# rc2014_MCP4822.net
KiCad netlist of a schematic drawn in EAGLE
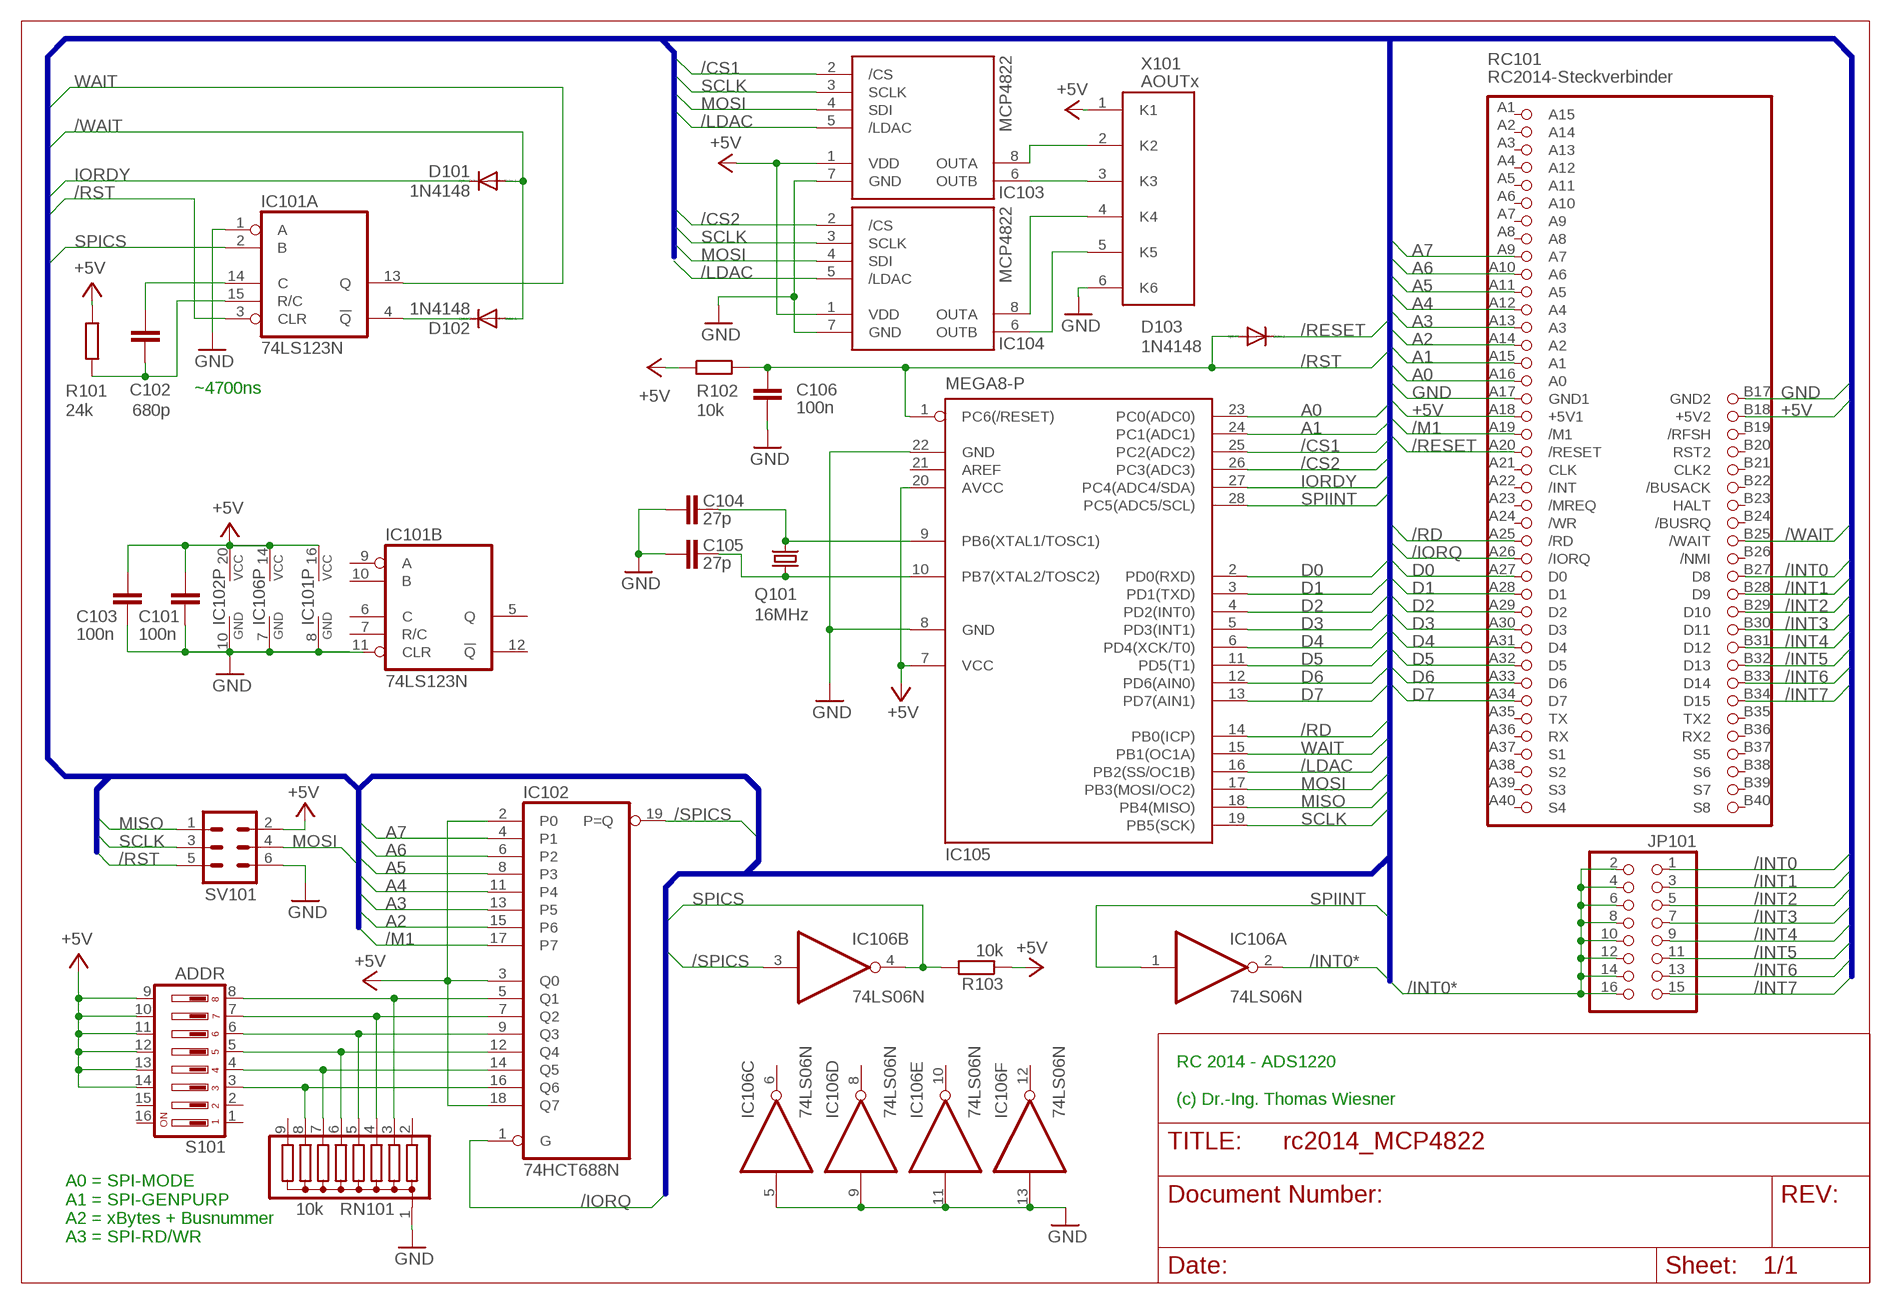
[diagram p0: schematic, sheet 1]

(export (version "E")
  (design (tool "Eeschema 10.0.6"))
  (components
    (comp (ref "C101")
      (value "100n")
      (footprint "eagle-import:C025-025X050")
      (libsource (lib "eagle-import") (part "C-EU025-025X050"))
    )
    (comp (ref "C102")
      (value "680p")
      (footprint "eagle-import:C025-025X050")
      (libsource (lib "eagle-import") (part "C-EU025-025X050"))
    )
    (comp (ref "C103")
      (value "100n")
      (footprint "eagle-import:C025-025X050")
      (libsource (lib "eagle-import") (part "C-EU025-025X050"))
    )
    (comp (ref "C104")
      (value "27p")
      (footprint "eagle-import:C025-025X050")
      (libsource (lib "eagle-import") (part "C-EU025-025X050"))
    )
    (comp (ref "C105")
      (value "27p")
      (footprint "eagle-import:C025-025X050")
      (libsource (lib "eagle-import") (part "C-EU025-025X050"))
    )
    (comp (ref "C106")
      (value "100n")
      (footprint "eagle-import:C025-025X050")
      (libsource (lib "eagle-import") (part "C-EU025-025X050"))
    )
    (comp (ref "D101")
      (value "1N4148")
      (footprint "eagle-import:DO35-10")
      (libsource (lib "eagle-import") (part "1N4148DO35-10"))
    )
    (comp (ref "D102")
      (value "1N4148")
      (footprint "eagle-import:DO35-10")
      (libsource (lib "eagle-import") (part "1N4148DO35-10"))
    )
    (comp (ref "D103")
      (value "1N4148")
      (footprint "eagle-import:DO35-10")
      (libsource (lib "eagle-import") (part "1N4148DO35-10"))
    )
    (comp (ref "IC101")
      (value "74LS123N")
      (footprint "eagle-import:DIL16")
      (libsource (lib "eagle-import") (part "74123NLS"))
    )
    (comp (ref "IC102")
      (value "74HCT688N")
      (footprint "eagle-import:DIL20")
      (libsource (lib "eagle-import") (part "74688NHCT"))
    )
    (comp (ref "IC103")
      (value "MCP4822")
      (footprint "eagle-import:DIL08")
      (libsource (lib "eagle-import") (part "MCP4822"))
    )
    (comp (ref "IC104")
      (value "MCP4822")
      (footprint "eagle-import:DIL08")
      (libsource (lib "eagle-import") (part "MCP4822"))
    )
    (comp (ref "IC105")
      (value "MEGA8-P")
      (footprint "eagle-import:DIL28-3")
      (libsource (lib "eagle-import") (part "MEGA8-P"))
    )
    (comp (ref "IC106")
      (value "74LS06N")
      (footprint "eagle-import:DIL14")
      (libsource (lib "eagle-import") (part "7406NLS"))
    )
    (comp (ref "JP101")
      (value "PINHD-2X8")
      (footprint "eagle-import:2X08")
      (libsource (lib "eagle-import") (part "PINHD-2X8"))
    )
    (comp (ref "Q101")
      (value "16MHz")
      (footprint "eagle-import:HC49U-V")
      (libsource (lib "eagle-import") (part "CRYSTALHC49U-V"))
    )
    (comp (ref "R101")
      (value "24k")
      (footprint "eagle-import:0207_10")
      (libsource (lib "eagle-import") (part "R-EU_0207/10"))
    )
    (comp (ref "R102")
      (value "10k")
      (footprint "eagle-import:0207_10")
      (libsource (lib "eagle-import") (part "R-EU_0207/10"))
    )
    (comp (ref "R103")
      (value "10k")
      (footprint "eagle-import:0207_10")
      (libsource (lib "eagle-import") (part "R-EU_0207/10"))
    )
    (comp (ref "RC101")
      (value "RC2014-Steckverbinder")
      (footprint "eagle-import:RC2014-STECKER")
      (libsource (lib "eagle-import") (part "RC2014STECKER"))
    )
    (comp (ref "RN101")
      (value "10k")
      (footprint "eagle-import:SIL9")
      (libsource (lib "eagle-import") (part "G08R"))
    )
    (comp (ref "S101")
      (value "ADDR")
      (footprint "eagle-import:DS-08")
      (fields (field (name "MPN") "DS08"))
      (libsource (lib "eagle-import") (part "DS08"))
    )
    (comp (ref "SV101")
      (value "ML6L")
      (footprint "eagle-import:ML6L")
      (libsource (lib "eagle-import") (part "ML6L"))
    )
    (comp (ref "X101")
      (value "AOUTx")
      (footprint "eagle-import:AKL182-6")
      (libsource (lib "eagle-import") (part "AKL182-6"))
    )
  )
  (nets
    (net (code "2") (name "+5V") (class "Default")
      (node (ref "C101") (pin "2") (pinfunction "2_2") (pintype "passive"))
      (node (ref "C103") (pin "2") (pinfunction "2_2") (pintype "passive"))
      (node (ref "IC101") (pin "16") (pinfunction "VCC_16") (pintype "power_in"))
      (node (ref "IC102") (pin "18") (pinfunction "Q7_18") (pintype "input"))
      (node (ref "IC102") (pin "2") (pinfunction "P0_2") (pintype "input"))
      (node (ref "IC102") (pin "20") (pinfunction "VCC_20") (pintype "power_in"))
      (node (ref "IC102") (pin "3") (pinfunction "Q0_3") (pintype "input"))
      (node (ref "IC103") (pin "1") (pinfunction "VDD_1") (pintype "bidirectional"))
      (node (ref "IC104") (pin "1") (pinfunction "VDD_1") (pintype "bidirectional"))
      (node (ref "IC105") (pin "20") (pinfunction "AVCC_20") (pintype "power_in"))
      (node (ref "IC105") (pin "7") (pinfunction "VCC_7") (pintype "power_in"))
      (node (ref "IC106") (pin "14") (pinfunction "VCC_14") (pintype "power_in"))
      (node (ref "R101") (pin "1") (pinfunction "1_1") (pintype "passive"))
      (node (ref "R102") (pin "1") (pinfunction "1_1") (pintype "passive"))
      (node (ref "R103") (pin "1") (pinfunction "1_1") (pintype "passive"))
      (node (ref "RC101") (pin "A18") (pinfunction "+5V1_A18") (pintype "passive"))
      (node (ref "RC101") (pin "B18") (pinfunction "+5V2_B18") (pintype "passive"))
      (node (ref "S101") (pin "10") (pinfunction "10_10") (pintype "passive"))
      (node (ref "S101") (pin "11") (pinfunction "11_11") (pintype "passive"))
      (node (ref "S101") (pin "12") (pinfunction "12_12") (pintype "passive"))
      (node (ref "S101") (pin "13") (pinfunction "13_13") (pintype "passive"))
      (node (ref "S101") (pin "14") (pinfunction "14_14") (pintype "passive"))
      (node (ref "S101") (pin "9") (pinfunction "9_9") (pintype "passive"))
      (node (ref "SV101") (pin "2") (pinfunction "2_2") (pintype "passive"))
      (node (ref "X101") (pin "1") (pinfunction "K1_1") (pintype "bidirectional"))
    )
    (net (code "3") (name "/A0") (class "Default")
      (node (ref "IC105") (pin "23") (pinfunction "PC0(ADC0)_23") (pintype "bidirectional"))
      (node (ref "RC101") (pin "A16") (pinfunction "A0_A16") (pintype "passive"))
    )
    (net (code "4") (name "/A1") (class "Default")
      (node (ref "IC105") (pin "24") (pinfunction "PC1(ADC1)_24") (pintype "bidirectional"))
      (node (ref "RC101") (pin "A15") (pinfunction "A1_A15") (pintype "passive"))
    )
    (net (code "5") (name "/A2") (class "Default")
      (node (ref "IC102") (pin "15") (pinfunction "P6_15") (pintype "input"))
      (node (ref "RC101") (pin "A14") (pinfunction "A2_A14") (pintype "passive"))
    )
    (net (code "6") (name "/A3") (class "Default")
      (node (ref "IC102") (pin "13") (pinfunction "P5_13") (pintype "input"))
      (node (ref "RC101") (pin "A13") (pinfunction "A3_A13") (pintype "passive"))
    )
    (net (code "7") (name "/A4") (class "Default")
      (node (ref "IC102") (pin "11") (pinfunction "P4_11") (pintype "input"))
      (node (ref "RC101") (pin "A12") (pinfunction "A4_A12") (pintype "passive"))
    )
    (net (code "8") (name "/A5") (class "Default")
      (node (ref "IC102") (pin "8") (pinfunction "P3_8") (pintype "input"))
      (node (ref "RC101") (pin "A11") (pinfunction "A5_A11") (pintype "passive"))
    )
    (net (code "9") (name "/A6") (class "Default")
      (node (ref "IC102") (pin "6") (pinfunction "P2_6") (pintype "input"))
      (node (ref "RC101") (pin "A10") (pinfunction "A6_A10") (pintype "passive"))
    )
    (net (code "10") (name "/A7") (class "Default")
      (node (ref "IC102") (pin "4") (pinfunction "P1_4") (pintype "input"))
      (node (ref "RC101") (pin "A9") (pinfunction "A7_A9") (pintype "passive"))
    )
    (net (code "11") (name "/D0") (class "Default")
      (node (ref "IC105") (pin "2") (pinfunction "PD0(RXD)_2") (pintype "bidirectional"))
      (node (ref "RC101") (pin "A27") (pinfunction "D0_A27") (pintype "passive"))
    )
    (net (code "12") (name "/D1") (class "Default")
      (node (ref "IC105") (pin "3") (pinfunction "PD1(TXD)_3") (pintype "bidirectional"))
      (node (ref "RC101") (pin "A28") (pinfunction "D1_A28") (pintype "passive"))
    )
    (net (code "13") (name "/D2") (class "Default")
      (node (ref "IC105") (pin "4") (pinfunction "PD2(INT0)_4") (pintype "bidirectional"))
      (node (ref "RC101") (pin "A29") (pinfunction "D2_A29") (pintype "passive"))
    )
    (net (code "14") (name "/D3") (class "Default")
      (node (ref "IC105") (pin "5") (pinfunction "PD3(INT1)_5") (pintype "bidirectional"))
      (node (ref "RC101") (pin "A30") (pinfunction "D3_A30") (pintype "passive"))
    )
    (net (code "15") (name "/D4") (class "Default")
      (node (ref "IC105") (pin "6") (pinfunction "PD4(XCK/T0)_6") (pintype "bidirectional"))
      (node (ref "RC101") (pin "A31") (pinfunction "D4_A31") (pintype "passive"))
    )
    (net (code "16") (name "/D5") (class "Default")
      (node (ref "IC105") (pin "11") (pinfunction "PD5(T1)_11") (pintype "bidirectional"))
      (node (ref "RC101") (pin "A32") (pinfunction "D5_A32") (pintype "passive"))
    )
    (net (code "17") (name "/D6") (class "Default")
      (node (ref "IC105") (pin "12") (pinfunction "PD6(AIN0)_12") (pintype "bidirectional"))
      (node (ref "RC101") (pin "A33") (pinfunction "D6_A33") (pintype "passive"))
    )
    (net (code "18") (name "/D7") (class "Default")
      (node (ref "IC105") (pin "13") (pinfunction "PD7(AIN1)_13") (pintype "bidirectional"))
      (node (ref "RC101") (pin "A34") (pinfunction "D7_A34") (pintype "passive"))
    )
    (net (code "19") (name "/IORDY") (class "Default")
      (node (ref "D101") (pin "C") (pinfunction "C_C") (pintype "passive"))
      (node (ref "IC105") (pin "27") (pinfunction "PC4(ADC4/SDA)_27") (pintype "bidirectional"))
    )
    (net (code "20") (name "/MISO") (class "Default")
      (node (ref "IC105") (pin "18") (pinfunction "PB4(MISO)_18") (pintype "bidirectional"))
      (node (ref "SV101") (pin "1") (pinfunction "1_1") (pintype "passive"))
    )
    (net (code "21") (name "/MOSI") (class "Default")
      (node (ref "IC103") (pin "4") (pinfunction "SDI_4") (pintype "bidirectional"))
      (node (ref "IC104") (pin "4") (pinfunction "SDI_4") (pintype "bidirectional"))
      (node (ref "IC105") (pin "17") (pinfunction "PB3(MOSI/OC2)_17") (pintype "bidirectional"))
      (node (ref "SV101") (pin "4") (pinfunction "4_4") (pintype "passive"))
    )
    (net (code "22") (name "/SCLK") (class "Default")
      (node (ref "IC103") (pin "3") (pinfunction "SCLK_3") (pintype "bidirectional"))
      (node (ref "IC104") (pin "3") (pinfunction "SCLK_3") (pintype "bidirectional"))
      (node (ref "IC105") (pin "19") (pinfunction "PB5(SCK)_19") (pintype "bidirectional"))
      (node (ref "SV101") (pin "3") (pinfunction "3_3") (pintype "passive"))
    )
    (net (code "23") (name "/SPICS") (class "Default")
      (node (ref "IC101") (pin "2") (pinfunction "B_2") (pintype "input"))
      (node (ref "IC106") (pin "4") (pinfunction "O_4") (pintype "open_collector"))
      (node (ref "R103") (pin "2") (pinfunction "2_2") (pintype "passive"))
    )
    (net (code "24") (name "/SPIINT") (class "Default")
      (node (ref "IC105") (pin "28") (pinfunction "PC5(ADC5/SCL)_28") (pintype "bidirectional"))
      (node (ref "IC106") (pin "1") (pinfunction "I_1") (pintype "input"))
    )
    (net (code "25") (name "/WAIT") (class "Default")
      (node (ref "IC101") (pin "13") (pinfunction "Q_13") (pintype "output"))
      (node (ref "IC105") (pin "15") (pinfunction "PB1(OC1A)_15") (pintype "bidirectional"))
    )
    (net (code "27") (name "/{slash}CS1") (class "Default")
      (node (ref "IC103") (pin "2") (pinfunction "/CS_2") (pintype "bidirectional"))
      (node (ref "IC105") (pin "25") (pinfunction "PC2(ADC2)_25") (pintype "bidirectional"))
    )
    (net (code "28") (name "/{slash}CS2") (class "Default")
      (node (ref "IC104") (pin "2") (pinfunction "/CS_2") (pintype "bidirectional"))
      (node (ref "IC105") (pin "26") (pinfunction "PC3(ADC3)_26") (pintype "bidirectional"))
    )
    (net (code "29") (name "/{slash}INT0") (class "Default")
      (node (ref "JP101") (pin "1") (pinfunction "1_1") (pintype "passive"))
      (node (ref "RC101") (pin "B27") (pinfunction "D8_B27") (pintype "passive"))
    )
    (net (code "30") (name "/{slash}INT0*") (class "Default")
      (node (ref "IC106") (pin "2") (pinfunction "O_2") (pintype "open_collector"))
      (node (ref "JP101") (pin "10") (pinfunction "10_10") (pintype "passive"))
      (node (ref "JP101") (pin "12") (pinfunction "12_12") (pintype "passive"))
      (node (ref "JP101") (pin "14") (pinfunction "14_14") (pintype "passive"))
      (node (ref "JP101") (pin "16") (pinfunction "16_16") (pintype "passive"))
      (node (ref "JP101") (pin "2") (pinfunction "2_2") (pintype "passive"))
      (node (ref "JP101") (pin "4") (pinfunction "4_4") (pintype "passive"))
      (node (ref "JP101") (pin "6") (pinfunction "6_6") (pintype "passive"))
      (node (ref "JP101") (pin "8") (pinfunction "8_8") (pintype "passive"))
    )
    (net (code "31") (name "/{slash}INT1") (class "Default")
      (node (ref "JP101") (pin "3") (pinfunction "3_3") (pintype "passive"))
      (node (ref "RC101") (pin "B28") (pinfunction "D9_B28") (pintype "passive"))
    )
    (net (code "32") (name "/{slash}INT2") (class "Default")
      (node (ref "JP101") (pin "5") (pinfunction "5_5") (pintype "passive"))
      (node (ref "RC101") (pin "B29") (pinfunction "D10_B29") (pintype "passive"))
    )
    (net (code "33") (name "/{slash}INT3") (class "Default")
      (node (ref "JP101") (pin "7") (pinfunction "7_7") (pintype "passive"))
      (node (ref "RC101") (pin "B30") (pinfunction "D11_B30") (pintype "passive"))
    )
    (net (code "34") (name "/{slash}INT4") (class "Default")
      (node (ref "JP101") (pin "9") (pinfunction "9_9") (pintype "passive"))
      (node (ref "RC101") (pin "B31") (pinfunction "D12_B31") (pintype "passive"))
    )
    (net (code "35") (name "/{slash}INT5") (class "Default")
      (node (ref "JP101") (pin "11") (pinfunction "11_11") (pintype "passive"))
      (node (ref "RC101") (pin "B32") (pinfunction "D13_B32") (pintype "passive"))
    )
    (net (code "36") (name "/{slash}INT6") (class "Default")
      (node (ref "JP101") (pin "13") (pinfunction "13_13") (pintype "passive"))
      (node (ref "RC101") (pin "B33") (pinfunction "D14_B33") (pintype "passive"))
    )
    (net (code "37") (name "/{slash}INT7") (class "Default")
      (node (ref "JP101") (pin "15") (pinfunction "15_15") (pintype "passive"))
      (node (ref "RC101") (pin "B34") (pinfunction "D15_B34") (pintype "passive"))
    )
    (net (code "38") (name "/{slash}IORQ") (class "Default")
      (node (ref "IC102") (pin "1") (pinfunction "G_1") (pintype "input"))
      (node (ref "RC101") (pin "A26") (pinfunction "/IORQ_A26") (pintype "passive"))
    )
    (net (code "39") (name "/{slash}LDAC") (class "Default")
      (node (ref "IC103") (pin "5") (pinfunction "/LDAC_5") (pintype "bidirectional"))
      (node (ref "IC104") (pin "5") (pinfunction "/LDAC_5") (pintype "bidirectional"))
      (node (ref "IC105") (pin "16") (pinfunction "PB2(SS/OC1B)_16") (pintype "bidirectional"))
    )
    (net (code "40") (name "/{slash}M1") (class "Default")
      (node (ref "IC102") (pin "17") (pinfunction "P7_17") (pintype "input"))
      (node (ref "RC101") (pin "A19") (pinfunction "/M1_A19") (pintype "passive"))
    )
    (net (code "41") (name "/{slash}RD") (class "Default")
      (node (ref "IC105") (pin "14") (pinfunction "PB0(ICP)_14") (pintype "bidirectional"))
      (node (ref "RC101") (pin "A25") (pinfunction "/RD_A25") (pintype "passive"))
    )
    (net (code "42") (name "/{slash}RESET") (class "Default")
      (node (ref "D103") (pin "C") (pinfunction "C_C") (pintype "passive"))
      (node (ref "RC101") (pin "A20") (pinfunction "/RESET_A20") (pintype "passive"))
    )
    (net (code "43") (name "/{slash}RST") (class "Default")
      (node (ref "C106") (pin "2") (pinfunction "2_2") (pintype "passive"))
      (node (ref "D103") (pin "A") (pinfunction "A_A") (pintype "passive"))
      (node (ref "IC101") (pin "3") (pinfunction "CLR_3") (pintype "input"))
      (node (ref "IC105") (pin "1") (pinfunction "PC6(/RESET)_1") (pintype "bidirectional"))
      (node (ref "R102") (pin "2") (pinfunction "2_2") (pintype "passive"))
      (node (ref "SV101") (pin "5") (pinfunction "5_5") (pintype "passive"))
    )
    (net (code "44") (name "/{slash}SPICS") (class "Default")
      (node (ref "IC102") (pin "19") (pinfunction "P=Q_19") (pintype "output"))
      (node (ref "IC106") (pin "3") (pinfunction "I_3") (pintype "input"))
    )
    (net (code "45") (name "/{slash}WAIT") (class "Default")
      (node (ref "D101") (pin "A") (pinfunction "A_A") (pintype "passive"))
      (node (ref "D102") (pin "A") (pinfunction "A_A") (pintype "passive"))
      (node (ref "RC101") (pin "B25") (pinfunction "/WAIT_B25") (pintype "passive"))
    )
    (net (code "46") (name "GND") (class "Default")
      (node (ref "C101") (pin "1") (pinfunction "1_1") (pintype "passive"))
      (node (ref "C103") (pin "1") (pinfunction "1_1") (pintype "passive"))
      (node (ref "C104") (pin "2") (pinfunction "2_2") (pintype "passive"))
      (node (ref "C105") (pin "2") (pinfunction "2_2") (pintype "passive"))
      (node (ref "C106") (pin "1") (pinfunction "1_1") (pintype "passive"))
      (node (ref "IC101") (pin "1") (pinfunction "A_1") (pintype "input"))
      (node (ref "IC101") (pin "11") (pinfunction "CLR_11") (pintype "input"))
      (node (ref "IC101") (pin "8") (pinfunction "GND_8") (pintype "power_in"))
      (node (ref "IC102") (pin "10") (pinfunction "GND_10") (pintype "power_in"))
      (node (ref "IC103") (pin "7") (pinfunction "GND_7") (pintype "bidirectional"))
      (node (ref "IC104") (pin "7") (pinfunction "GND_7") (pintype "bidirectional"))
      (node (ref "IC105") (pin "22") (pinfunction "GND_22") (pintype "power_in"))
      (node (ref "IC105") (pin "8") (pinfunction "GND_8") (pintype "power_in"))
      (node (ref "IC106") (pin "11") (pinfunction "I_11") (pintype "input"))
      (node (ref "IC106") (pin "13") (pinfunction "I_13") (pintype "input"))
      (node (ref "IC106") (pin "5") (pinfunction "I_5") (pintype "input"))
      (node (ref "IC106") (pin "7") (pinfunction "GND_7") (pintype "power_in"))
      (node (ref "IC106") (pin "9") (pinfunction "I_9") (pintype "input"))
      (node (ref "RC101") (pin "A17") (pinfunction "GND1_A17") (pintype "passive"))
      (node (ref "RC101") (pin "B17") (pinfunction "GND2_B17") (pintype "passive"))
      (node (ref "RN101") (pin "1") (pinfunction "1_1") (pintype "passive"))
      (node (ref "SV101") (pin "6") (pinfunction "6_6") (pintype "passive"))
      (node (ref "X101") (pin "6") (pinfunction "K6_6") (pintype "bidirectional"))
    )
    (net (code "47") (name "Net-(IC101A-C)") (class "Default")
      (node (ref "C102") (pin "2") (pinfunction "2_2") (pintype "passive"))
      (node (ref "IC101") (pin "14") (pinfunction "C_14") (pintype "input"))
    )
    (net (code "48") (name "Net-(IC101A-R{slash}C)") (class "Default")
      (node (ref "C102") (pin "1") (pinfunction "1_1") (pintype "passive"))
      (node (ref "IC101") (pin "15") (pinfunction "R/C_15") (pintype "input"))
      (node (ref "R101") (pin "2") (pinfunction "2_2") (pintype "passive"))
    )
    (net (code "49") (name "Net-(IC101A-~{Q})") (class "Default")
      (node (ref "D102") (pin "C") (pinfunction "C_C") (pintype "passive"))
      (node (ref "IC101") (pin "4") (pinfunction "~{Q}_4") (pintype "output"))
    )
    (net (code "50") (name "Net-(IC102A-Q1)") (class "Default")
      (node (ref "IC102") (pin "5") (pinfunction "Q1_5") (pintype "input"))
      (node (ref "RN101") (pin "3") (pinfunction "3_3") (pintype "passive"))
      (node (ref "S101") (pin "8") (pinfunction "8_8") (pintype "passive"))
    )
    (net (code "51") (name "Net-(IC102A-Q2)") (class "Default")
      (node (ref "IC102") (pin "7") (pinfunction "Q2_7") (pintype "input"))
      (node (ref "RN101") (pin "4") (pinfunction "4_4") (pintype "passive"))
      (node (ref "S101") (pin "7") (pinfunction "7_7") (pintype "passive"))
    )
    (net (code "52") (name "Net-(IC102A-Q3)") (class "Default")
      (node (ref "IC102") (pin "9") (pinfunction "Q3_9") (pintype "input"))
      (node (ref "RN101") (pin "5") (pinfunction "5_5") (pintype "passive"))
      (node (ref "S101") (pin "6") (pinfunction "6_6") (pintype "passive"))
    )
    (net (code "53") (name "Net-(IC102A-Q4)") (class "Default")
      (node (ref "IC102") (pin "12") (pinfunction "Q4_12") (pintype "input"))
      (node (ref "RN101") (pin "6") (pinfunction "6_6") (pintype "passive"))
      (node (ref "S101") (pin "5") (pinfunction "5_5") (pintype "passive"))
    )
    (net (code "54") (name "Net-(IC102A-Q5)") (class "Default")
      (node (ref "IC102") (pin "14") (pinfunction "Q5_14") (pintype "input"))
      (node (ref "RN101") (pin "7") (pinfunction "7_7") (pintype "passive"))
      (node (ref "S101") (pin "4") (pinfunction "4_4") (pintype "passive"))
    )
    (net (code "55") (name "Net-(IC102A-Q6)") (class "Default")
      (node (ref "IC102") (pin "16") (pinfunction "Q6_16") (pintype "input"))
      (node (ref "RN101") (pin "8") (pinfunction "8_8") (pintype "passive"))
      (node (ref "S101") (pin "3") (pinfunction "3_3") (pintype "passive"))
    )
    (net (code "56") (name "Net-(IC103-OUTA)") (class "Default")
      (node (ref "IC103") (pin "8") (pinfunction "OUTA_8") (pintype "bidirectional"))
      (node (ref "X101") (pin "2") (pinfunction "K2_2") (pintype "bidirectional"))
    )
    (net (code "57") (name "Net-(IC103-OUTB)") (class "Default")
      (node (ref "IC103") (pin "6") (pinfunction "OUTB_6") (pintype "bidirectional"))
      (node (ref "X101") (pin "3") (pinfunction "K3_3") (pintype "bidirectional"))
    )
    (net (code "58") (name "Net-(IC104-OUTA)") (class "Default")
      (node (ref "IC104") (pin "8") (pinfunction "OUTA_8") (pintype "bidirectional"))
      (node (ref "X101") (pin "4") (pinfunction "K4_4") (pintype "bidirectional"))
    )
    (net (code "59") (name "Net-(IC104-OUTB)") (class "Default")
      (node (ref "IC104") (pin "6") (pinfunction "OUTB_6") (pintype "bidirectional"))
      (node (ref "X101") (pin "5") (pinfunction "K5_5") (pintype "bidirectional"))
    )
    (net (code "60") (name "Net-(IC105-PB6(XTAL1{slash}TOSC1))") (class "Default")
      (node (ref "C104") (pin "1") (pinfunction "1_1") (pintype "passive"))
      (node (ref "IC105") (pin "9") (pinfunction "PB6(XTAL1/TOSC1)_9") (pintype "bidirectional"))
      (node (ref "Q101") (pin "2") (pinfunction "2_2") (pintype "passive"))
    )
    (net (code "61") (name "Net-(IC105-PB7(XTAL2{slash}TOSC2))") (class "Default")
      (node (ref "C105") (pin "1") (pinfunction "1_1") (pintype "passive"))
      (node (ref "IC105") (pin "10") (pinfunction "PB7(XTAL2/TOSC2)_10") (pintype "bidirectional"))
      (node (ref "Q101") (pin "1") (pinfunction "1_1") (pintype "passive"))
    )
    (net (code "62") (name "unconnected-(IC101B-A-Pad9)") (class "Default")
      (node (ref "IC101") (pin "9") (pinfunction "A_9") (pintype "input"))
    )
    (net (code "63") (name "unconnected-(IC101B-B-Pad10)") (class "Default")
      (node (ref "IC101") (pin "10") (pinfunction "B_10") (pintype "input"))
    )
    (net (code "64") (name "unconnected-(IC101B-C-Pad6)") (class "Default")
      (node (ref "IC101") (pin "6") (pinfunction "C_6") (pintype "input"))
    )
    (net (code "65") (name "unconnected-(IC101B-Q-Pad5)") (class "Default")
      (node (ref "IC101") (pin "5") (pinfunction "Q_5") (pintype "output"))
    )
    (net (code "66") (name "unconnected-(IC101B-R{slash}C-Pad7)") (class "Default")
      (node (ref "IC101") (pin "7") (pinfunction "R/C_7") (pintype "input"))
    )
    (net (code "67") (name "unconnected-(IC101B-~{Q}-Pad12)") (class "Default")
      (node (ref "IC101") (pin "12") (pinfunction "~{Q}_12") (pintype "output"))
    )
    (net (code "68") (name "unconnected-(IC105-AREF-Pad21)") (class "Default")
      (node (ref "IC105") (pin "21") (pinfunction "AREF_21") (pintype "passive"))
    )
    (net (code "69") (name "unconnected-(IC106C-O-Pad6)") (class "Default")
      (node (ref "IC106") (pin "6") (pinfunction "O_6") (pintype "open_collector"))
    )
    (net (code "70") (name "unconnected-(IC106D-O-Pad8)") (class "Default")
      (node (ref "IC106") (pin "8") (pinfunction "O_8") (pintype "open_collector"))
    )
    (net (code "71") (name "unconnected-(IC106E-O-Pad10)") (class "Default")
      (node (ref "IC106") (pin "10") (pinfunction "O_10") (pintype "open_collector"))
    )
    (net (code "72") (name "unconnected-(IC106F-O-Pad12)") (class "Default")
      (node (ref "IC106") (pin "12") (pinfunction "O_12") (pintype "open_collector"))
    )
    (net (code "73") (name "unconnected-(RC101-A9-PadA7)") (class "Default")
      (node (ref "RC101") (pin "A7") (pinfunction "A9_A7") (pintype "passive"))
    )
    (net (code "74") (name "unconnected-(RC101-A10-PadA6)") (class "Default")
      (node (ref "RC101") (pin "A6") (pinfunction "A10_A6") (pintype "passive"))
    )
    (net (code "75") (name "unconnected-(RC101-A11-PadA5)") (class "Default")
      (node (ref "RC101") (pin "A5") (pinfunction "A11_A5") (pintype "passive"))
    )
    (net (code "76") (name "unconnected-(RC101-A12-PadA4)") (class "Default")
      (node (ref "RC101") (pin "A4") (pinfunction "A12_A4") (pintype "passive"))
    )
    (net (code "77") (name "unconnected-(RC101-A13-PadA3)") (class "Default")
      (node (ref "RC101") (pin "A3") (pinfunction "A13_A3") (pintype "passive"))
    )
    (net (code "78") (name "unconnected-(RC101-A14-PadA2)") (class "Default")
      (node (ref "RC101") (pin "A2") (pinfunction "A14_A2") (pintype "passive"))
    )
    (net (code "79") (name "unconnected-(RC101-A15-PadA1)") (class "Default")
      (node (ref "RC101") (pin "A1") (pinfunction "A15_A1") (pintype "passive"))
    )
    (net (code "80") (name "unconnected-(RC101-CLK-PadA21)") (class "Default")
      (node (ref "RC101") (pin "A21") (pinfunction "CLK_A21") (pintype "passive"))
    )
    (net (code "81") (name "unconnected-(RC101-CLK2-PadB21)") (class "Default")
      (node (ref "RC101") (pin "B21") (pinfunction "CLK2_B21") (pintype "passive"))
    )
    (net (code "82") (name "unconnected-(RC101-HALT-PadB23)") (class "Default")
      (node (ref "RC101") (pin "B23") (pinfunction "HALT_B23") (pintype "passive"))
    )
    (net (code "83") (name "unconnected-(RC101-PadA8)") (class "Default")
      (node (ref "RC101") (pin "A8") (pinfunction "A8_A8") (pintype "passive"))
    )
    (net (code "84") (name "unconnected-(RC101-RST2-PadB20)") (class "Default")
      (node (ref "RC101") (pin "B20") (pinfunction "RST2_B20") (pintype "passive"))
    )
    (net (code "85") (name "unconnected-(RC101-RX-PadA36)") (class "Default")
      (node (ref "RC101") (pin "A36") (pinfunction "RX_A36") (pintype "passive"))
    )
    (net (code "86") (name "unconnected-(RC101-RX2-PadB36)") (class "Default")
      (node (ref "RC101") (pin "B36") (pinfunction "RX2_B36") (pintype "passive"))
    )
    (net (code "87") (name "unconnected-(RC101-S1-PadA37)") (class "Default")
      (node (ref "RC101") (pin "A37") (pinfunction "S1_A37") (pintype "passive"))
    )
    (net (code "88") (name "unconnected-(RC101-S2-PadA38)") (class "Default")
      (node (ref "RC101") (pin "A38") (pinfunction "S2_A38") (pintype "passive"))
    )
    (net (code "89") (name "unconnected-(RC101-S3-PadA39)") (class "Default")
      (node (ref "RC101") (pin "A39") (pinfunction "S3_A39") (pintype "passive"))
    )
    (net (code "90") (name "unconnected-(RC101-S4-PadA40)") (class "Default")
      (node (ref "RC101") (pin "A40") (pinfunction "S4_A40") (pintype "passive"))
    )
    (net (code "91") (name "unconnected-(RC101-S5-PadB37)") (class "Default")
      (node (ref "RC101") (pin "B37") (pinfunction "S5_B37") (pintype "passive"))
    )
    (net (code "92") (name "unconnected-(RC101-S6-PadB38)") (class "Default")
      (node (ref "RC101") (pin "B38") (pinfunction "S6_B38") (pintype "passive"))
    )
    (net (code "93") (name "unconnected-(RC101-S7-PadB39)") (class "Default")
      (node (ref "RC101") (pin "B39") (pinfunction "S7_B39") (pintype "passive"))
    )
    (net (code "94") (name "unconnected-(RC101-S8-PadB40)") (class "Default")
      (node (ref "RC101") (pin "B40") (pinfunction "S8_B40") (pintype "passive"))
    )
    (net (code "95") (name "unconnected-(RC101-TX-PadA35)") (class "Default")
      (node (ref "RC101") (pin "A35") (pinfunction "TX_A35") (pintype "passive"))
    )
    (net (code "96") (name "unconnected-(RC101-TX2-PadB35)") (class "Default")
      (node (ref "RC101") (pin "B35") (pinfunction "TX2_B35") (pintype "passive"))
    )
    (net (code "97") (name "unconnected-(RC101-{slash}BUSACK-PadB22)") (class "Default")
      (node (ref "RC101") (pin "B22") (pinfunction "/BUSACK_B22") (pintype "passive"))
    )
    (net (code "98") (name "unconnected-(RC101-{slash}BUSRQ-PadB24)") (class "Default")
      (node (ref "RC101") (pin "B24") (pinfunction "/BUSRQ_B24") (pintype "passive"))
    )
    (net (code "99") (name "unconnected-(RC101-{slash}INT-PadA22)") (class "Default")
      (node (ref "RC101") (pin "A22") (pinfunction "/INT_A22") (pintype "passive"))
    )
    (net (code "100") (name "unconnected-(RC101-{slash}MREQ-PadA23)") (class "Default")
      (node (ref "RC101") (pin "A23") (pinfunction "/MREQ_A23") (pintype "passive"))
    )
    (net (code "101") (name "unconnected-(RC101-{slash}NMI-PadB26)") (class "Default")
      (node (ref "RC101") (pin "B26") (pinfunction "/NMI_B26") (pintype "passive"))
    )
    (net (code "102") (name "unconnected-(RC101-{slash}RFSH-PadB19)") (class "Default")
      (node (ref "RC101") (pin "B19") (pinfunction "/RFSH_B19") (pintype "passive"))
    )
    (net (code "103") (name "unconnected-(RC101-{slash}WR-PadA24)") (class "Default")
      (node (ref "RC101") (pin "A24") (pinfunction "/WR_A24") (pintype "passive"))
    )
    (net (code "104") (name "unconnected-(RN101-Pad2)") (class "Default")
      (node (ref "RN101") (pin "2") (pinfunction "2_2") (pintype "passive"))
    )
    (net (code "105") (name "unconnected-(RN101-Pad9)") (class "Default")
      (node (ref "RN101") (pin "9") (pinfunction "9_9") (pintype "passive"))
    )
    (net (code "106") (name "unconnected-(S101-Pad1)") (class "Default")
      (node (ref "S101") (pin "1") (pinfunction "1_1") (pintype "passive"))
    )
    (net (code "107") (name "unconnected-(S101-Pad2)") (class "Default")
      (node (ref "S101") (pin "2") (pinfunction "2_2") (pintype "passive"))
    )
    (net (code "108") (name "unconnected-(S101-Pad15)") (class "Default")
      (node (ref "S101") (pin "15") (pinfunction "15_15") (pintype "passive"))
    )
    (net (code "109") (name "unconnected-(S101-Pad16)") (class "Default")
      (node (ref "S101") (pin "16") (pinfunction "16_16") (pintype "passive"))
    )
  )
)
